# maze_poke_1_0.net
KiCad netlist of a schematic drawn in EAGLE
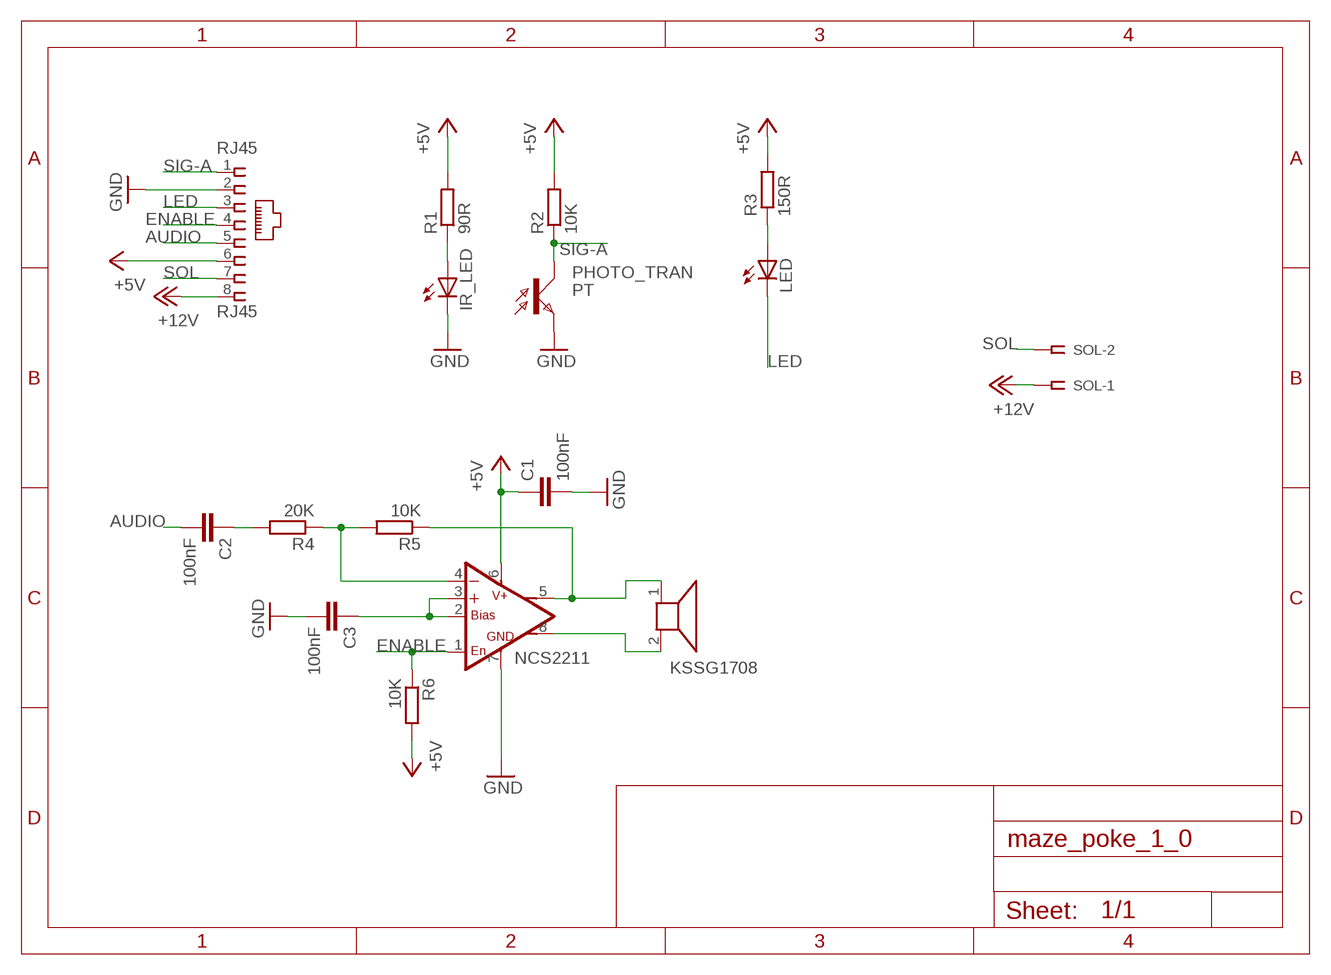
[diagram p0: schematic, sheet 1]

(export (version "E")
  (design (tool "Eeschema 10.0.6"))
  (components
    (comp (ref "C1")
      (value "100nF")
      (footprint "eagle-import:C0805")
      (libsource (lib "eagle-import") (part "C-EUC0805"))
    )
    (comp (ref "C2")
      (value "100nF")
      (footprint "eagle-import:C0805")
      (libsource (lib "eagle-import") (part "C-EUC0805"))
    )
    (comp (ref "C3")
      (value "100nF")
      (footprint "eagle-import:C0805")
      (libsource (lib "eagle-import") (part "C-EUC0805"))
    )
    (comp (ref "IR_LED")
      (value "LEDIRL80A")
      (footprint "eagle-import:IRL80A")
      (libsource (lib "eagle-import") (part "LEDIRL80A"))
    )
    (comp (ref "LED")
      (value "LEDSML0805")
      (footprint "eagle-import:SML0805")
      (libsource (lib "eagle-import") (part "LEDSML0805"))
    )
    (comp (ref "NCS2211")
      (value "NCS22111M")
      (footprint "eagle-import:SO08")
      (libsource (lib "eagle-import") (part "NCS2211M1"))
    )
    (comp (ref "PHOTO_TRAN")
      (value "PT")
      (footprint "eagle-import:LPT80A")
      (fields (field (name "OC_FARNELL") "unknown") (field (name "OC_NEWARK") "unknown"))
      (libsource (lib "eagle-import") (part "LPT80A"))
    )
    (comp (ref "R1")
      (value "90R")
      (footprint "eagle-import:R0805")
      (libsource (lib "eagle-import") (part "R-EU_R0805"))
    )
    (comp (ref "R2")
      (value "10K")
      (footprint "eagle-import:M0805")
      (libsource (lib "eagle-import") (part "R-EU_M0805"))
    )
    (comp (ref "R3")
      (value "150R")
      (footprint "eagle-import:M0805")
      (libsource (lib "eagle-import") (part "R-EU_M0805"))
    )
    (comp (ref "R4")
      (value "20K")
      (footprint "eagle-import:M0805")
      (libsource (lib "eagle-import") (part "R-EU_M0805"))
    )
    (comp (ref "R5")
      (value "10K")
      (footprint "eagle-import:M0805")
      (libsource (lib "eagle-import") (part "R-EU_M0805"))
    )
    (comp (ref "R6")
      (value "10K")
      (footprint "eagle-import:M0805")
      (libsource (lib "eagle-import") (part "R-EU_M0805"))
    )
    (comp (ref "RJ45")
      (value "RJ45")
      (footprint "eagle-import:RJ45-NO-SHIELD-VERTICAL")
      (libsource (lib "eagle-import") (part "RJ45VERTICAL"))
    )
    (comp (ref "SOL")
      (value "SSW-102-02-S-S-RA")
      (footprint "eagle-import:SSW-102-02-S-S-RA")
      (libsource (lib "eagle-import") (part "SSW-102-02-S-S-RA"))
    )
    (comp (ref "U$1")
      (value "KSSG1708")
      (footprint "eagle-import:KSSG1708")
      (libsource (lib "eagle-import") (part "KSSG1708"))
    )
  )
  (nets
    (net (code "1") (name "+5V") (class "Default")
      (node (ref "C1") (pin "1") (pinfunction "1_1") (pintype "passive"))
      (node (ref "NCS2211") (pin "6") (pinfunction "VS_6") (pintype "power_in"))
      (node (ref "R1") (pin "2") (pinfunction "2_2") (pintype "passive"))
      (node (ref "R2") (pin "2") (pinfunction "2_2") (pintype "passive"))
      (node (ref "R3") (pin "2") (pinfunction "2_2") (pintype "passive"))
      (node (ref "R6") (pin "2") (pinfunction "2_2") (pintype "passive"))
      (node (ref "RJ45") (pin "6") (pinfunction "6_6") (pintype "passive"))
    )
    (net (code "2") (name "+12V") (class "Default")
      (node (ref "RJ45") (pin "8") (pinfunction "8_8") (pintype "passive"))
      (node (ref "SOL") (pin "1") (pinfunction "1_1") (pintype "passive"))
    )
    (net (code "3") (name "/AUDIO") (class "Default")
      (node (ref "C2") (pin "2") (pinfunction "2_2") (pintype "passive"))
      (node (ref "RJ45") (pin "5") (pinfunction "5_5") (pintype "passive"))
    )
    (net (code "4") (name "/ENABLE") (class "Default")
      (node (ref "NCS2211") (pin "1") (pinfunction "ENABLE_1") (pintype "passive"))
      (node (ref "R6") (pin "1") (pinfunction "1_1") (pintype "passive"))
      (node (ref "RJ45") (pin "4") (pinfunction "4_4") (pintype "passive"))
    )
    (net (code "5") (name "/LED") (class "Default")
      (node (ref "LED") (pin "C") (pinfunction "C_C") (pintype "passive"))
      (node (ref "RJ45") (pin "3") (pinfunction "3_3") (pintype "passive"))
    )
    (net (code "6") (name "/SIG-A") (class "Default")
      (node (ref "PHOTO_TRAN") (pin "C") (pinfunction "C_C") (pintype "passive"))
      (node (ref "R2") (pin "1") (pinfunction "1_1") (pintype "passive"))
      (node (ref "RJ45") (pin "1") (pinfunction "1_1") (pintype "passive"))
    )
    (net (code "7") (name "/SOL") (class "Default")
      (node (ref "RJ45") (pin "7") (pinfunction "7_7") (pintype "passive"))
      (node (ref "SOL") (pin "2") (pinfunction "1_2") (pintype "passive"))
    )
    (net (code "8") (name "GND") (class "Default")
      (node (ref "C1") (pin "2") (pinfunction "2_2") (pintype "passive"))
      (node (ref "C3") (pin "2") (pinfunction "2_2") (pintype "passive"))
      (node (ref "IR_LED") (pin "K") (pinfunction "C_K") (pintype "passive"))
      (node (ref "NCS2211") (pin "7") (pinfunction "GND_7") (pintype "power_in"))
      (node (ref "PHOTO_TRAN") (pin "E") (pinfunction "E_E") (pintype "passive"))
      (node (ref "RJ45") (pin "2") (pinfunction "2_2") (pintype "passive"))
    )
    (net (code "9") (name "Net-(C2-Pad1)") (class "Default")
      (node (ref "C2") (pin "1") (pinfunction "1_1") (pintype "passive"))
      (node (ref "R4") (pin "2") (pinfunction "2_2") (pintype "passive"))
    )
    (net (code "10") (name "Net-(IR_LED-PadA)") (class "Default")
      (node (ref "IR_LED") (pin "A") (pinfunction "A_A") (pintype "passive"))
      (node (ref "R1") (pin "1") (pinfunction "1_1") (pintype "passive"))
    )
    (net (code "11") (name "Net-(LED-PadA)") (class "Default")
      (node (ref "LED") (pin "A") (pinfunction "A_A") (pintype "passive"))
      (node (ref "R3") (pin "1") (pinfunction "1_1") (pintype "passive"))
    )
    (net (code "12") (name "Net-(NCS2211-+IN)") (class "Default")
      (node (ref "C3") (pin "1") (pinfunction "1_1") (pintype "passive"))
      (node (ref "NCS2211") (pin "2") (pinfunction "BIAS_2") (pintype "passive"))
      (node (ref "NCS2211") (pin "3") (pinfunction "+IN_3") (pintype "input"))
    )
    (net (code "13") (name "Net-(NCS2211-+OUT)") (class "Default")
      (node (ref "NCS2211") (pin "5") (pinfunction "+OUT_5") (pintype "passive"))
      (node (ref "R5") (pin "1") (pinfunction "1_1") (pintype "passive"))
      (node (ref "U$1") (pin "1") (pinfunction "1_1") (pintype "passive"))
    )
    (net (code "14") (name "Net-(NCS2211--IN)") (class "Default")
      (node (ref "NCS2211") (pin "4") (pinfunction "-IN_4") (pintype "input"))
      (node (ref "R4") (pin "1") (pinfunction "1_1") (pintype "passive"))
      (node (ref "R5") (pin "2") (pinfunction "2_2") (pintype "passive"))
    )
    (net (code "15") (name "Net-(NCS2211--OUT)") (class "Default")
      (node (ref "NCS2211") (pin "8") (pinfunction "-OUT_8") (pintype "output"))
      (node (ref "U$1") (pin "2") (pinfunction "2_2") (pintype "passive"))
    )
  )
)
